# controller.net
KiCad netlist of a schematic drawn in Altium Designer
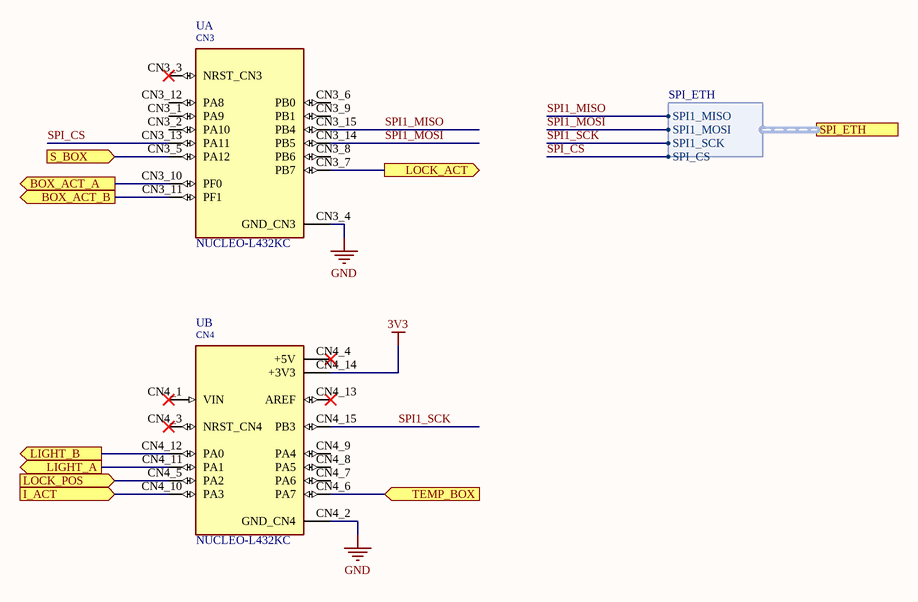
[diagram p0: controller.SchDoc]

(export (version "E")
  (design (tool "Eeschema 10.0.6"))
  (components
    (comp (ref "U")
      (value "NUCLEO-L432KC")
      (footprint "MODULE_NUCLEO-L432KC")
      (fields (field (name "MF") "STMicroelectronics"))
      (libsource (lib "food_box") (part "NUCLEO-L432KC"))
    )
  )
  (nets
    (net (code "2") (name "/BOX_ACT_A") (class "Default")
      (node (ref "U") (pin "CN3_10") (pinfunction "PF0_CN3_10") (pintype "bidirectional"))
    )
    (net (code "3") (name "/BOX_ACT_B") (class "Default")
      (node (ref "U") (pin "CN3_11") (pinfunction "PF1_CN3_11") (pintype "bidirectional"))
    )
    (net (code "4") (name "/I_ACT") (class "Default")
      (node (ref "U") (pin "CN4_10") (pinfunction "PA3_CN4_10") (pintype "bidirectional"))
    )
    (net (code "5") (name "/LIGHT_A") (class "Default")
      (node (ref "U") (pin "CN4_11") (pinfunction "PA1_CN4_11") (pintype "bidirectional"))
    )
    (net (code "6") (name "/LIGHT_B") (class "Default")
      (node (ref "U") (pin "CN4_12") (pinfunction "PA0_CN4_12") (pintype "bidirectional"))
    )
    (net (code "7") (name "/LOCK_ACT") (class "Default")
      (node (ref "U") (pin "CN3_7") (pinfunction "PB7_CN3_7") (pintype "bidirectional"))
    )
    (net (code "8") (name "/LOCK_POS") (class "Default")
      (node (ref "U") (pin "CN4_5") (pinfunction "PA2_CN4_5") (pintype "bidirectional"))
    )
    (net (code "9") (name "/SPI1_MISO") (class "Default")
      (node (ref "U") (pin "CN3_15") (pinfunction "PB4_CN3_15") (pintype "bidirectional"))
    )
    (net (code "10") (name "/SPI1_MOSI") (class "Default")
      (node (ref "U") (pin "CN3_14") (pinfunction "PB5_CN3_14") (pintype "bidirectional"))
    )
    (net (code "11") (name "/SPI1_SCK") (class "Default")
      (node (ref "U") (pin "CN4_15") (pinfunction "PB3_CN4_15") (pintype "bidirectional"))
    )
    (net (code "12") (name "/SPI_CS") (class "Default")
      (node (ref "U") (pin "CN3_13") (pinfunction "PA11_CN3_13") (pintype "bidirectional"))
    )
    (net (code "13") (name "/S_BOX") (class "Default")
      (node (ref "U") (pin "CN3_5") (pinfunction "PA12_CN3_5") (pintype "bidirectional"))
    )
    (net (code "14") (name "/TEMP_BOX") (class "Default")
      (node (ref "U") (pin "CN4_6") (pinfunction "PA7_CN4_6") (pintype "bidirectional"))
    )
    (net (code "16") (name "3V3") (class "Default")
      (node (ref "U") (pin "CN4_14") (pinfunction "+3V3_CN4_14") (pintype "power_in"))
    )
    (net (code "17") (name "GND") (class "Default")
      (node (ref "U") (pin "CN3_4") (pinfunction "GND_CN3_CN3_4") (pintype "power_in"))
      (node (ref "U") (pin "CN4_2") (pinfunction "GND_CN4_CN4_2") (pintype "power_in"))
    )
    (net (code "18") (name "unconnected-(UA-NRST_CN3-PadCN3_3)") (class "Default")
      (node (ref "U") (pin "CN3_3") (pinfunction "NRST_CN3_CN3_3") (pintype "bidirectional+no_connect"))
    )
    (net (code "19") (name "unconnected-(UA-PA8-PadCN3_12)") (class "Default")
      (node (ref "U") (pin "CN3_12") (pinfunction "PA8_CN3_12") (pintype "bidirectional"))
    )
    (net (code "20") (name "unconnected-(UA-PA9-PadCN3_1)") (class "Default")
      (node (ref "U") (pin "CN3_1") (pinfunction "PA9_CN3_1") (pintype "bidirectional"))
    )
    (net (code "21") (name "unconnected-(UA-PA10-PadCN3_2)") (class "Default")
      (node (ref "U") (pin "CN3_2") (pinfunction "PA10_CN3_2") (pintype "bidirectional"))
    )
    (net (code "22") (name "unconnected-(UA-PB0-PadCN3_6)") (class "Default")
      (node (ref "U") (pin "CN3_6") (pinfunction "PB0_CN3_6") (pintype "bidirectional"))
    )
    (net (code "23") (name "unconnected-(UA-PB1-PadCN3_9)") (class "Default")
      (node (ref "U") (pin "CN3_9") (pinfunction "PB1_CN3_9") (pintype "bidirectional"))
    )
    (net (code "24") (name "unconnected-(UA-PB6-PadCN3_8)") (class "Default")
      (node (ref "U") (pin "CN3_8") (pinfunction "PB6_CN3_8") (pintype "bidirectional"))
    )
    (net (code "25") (name "unconnected-(UB-+5V-PadCN4_4)") (class "Default")
      (node (ref "U") (pin "CN4_4") (pinfunction "+5V_CN4_4") (pintype "power_in+no_connect"))
    )
    (net (code "26") (name "unconnected-(UB-AREF-PadCN4_13)") (class "Default")
      (node (ref "U") (pin "CN4_13") (pinfunction "AREF_CN4_13") (pintype "bidirectional+no_connect"))
    )
    (net (code "27") (name "unconnected-(UB-NRST_CN4-PadCN4_3)") (class "Default")
      (node (ref "U") (pin "CN4_3") (pinfunction "NRST_CN4_CN4_3") (pintype "bidirectional+no_connect"))
    )
    (net (code "28") (name "unconnected-(UB-PA4-PadCN4_9)") (class "Default")
      (node (ref "U") (pin "CN4_9") (pinfunction "PA4_CN4_9") (pintype "bidirectional"))
    )
    (net (code "29") (name "unconnected-(UB-PA5-PadCN4_8)") (class "Default")
      (node (ref "U") (pin "CN4_8") (pinfunction "PA5_CN4_8") (pintype "bidirectional"))
    )
    (net (code "30") (name "unconnected-(UB-PA6-PadCN4_7)") (class "Default")
      (node (ref "U") (pin "CN4_7") (pinfunction "PA6_CN4_7") (pintype "bidirectional"))
    )
    (net (code "31") (name "unconnected-(UB-VIN-PadCN4_1)") (class "Default")
      (node (ref "U") (pin "CN4_1") (pinfunction "VIN_CN4_1") (pintype "input+no_connect"))
    )
  )
)
